# nabijecka.net
KiCad netlist of a schematic drawn in EAGLE
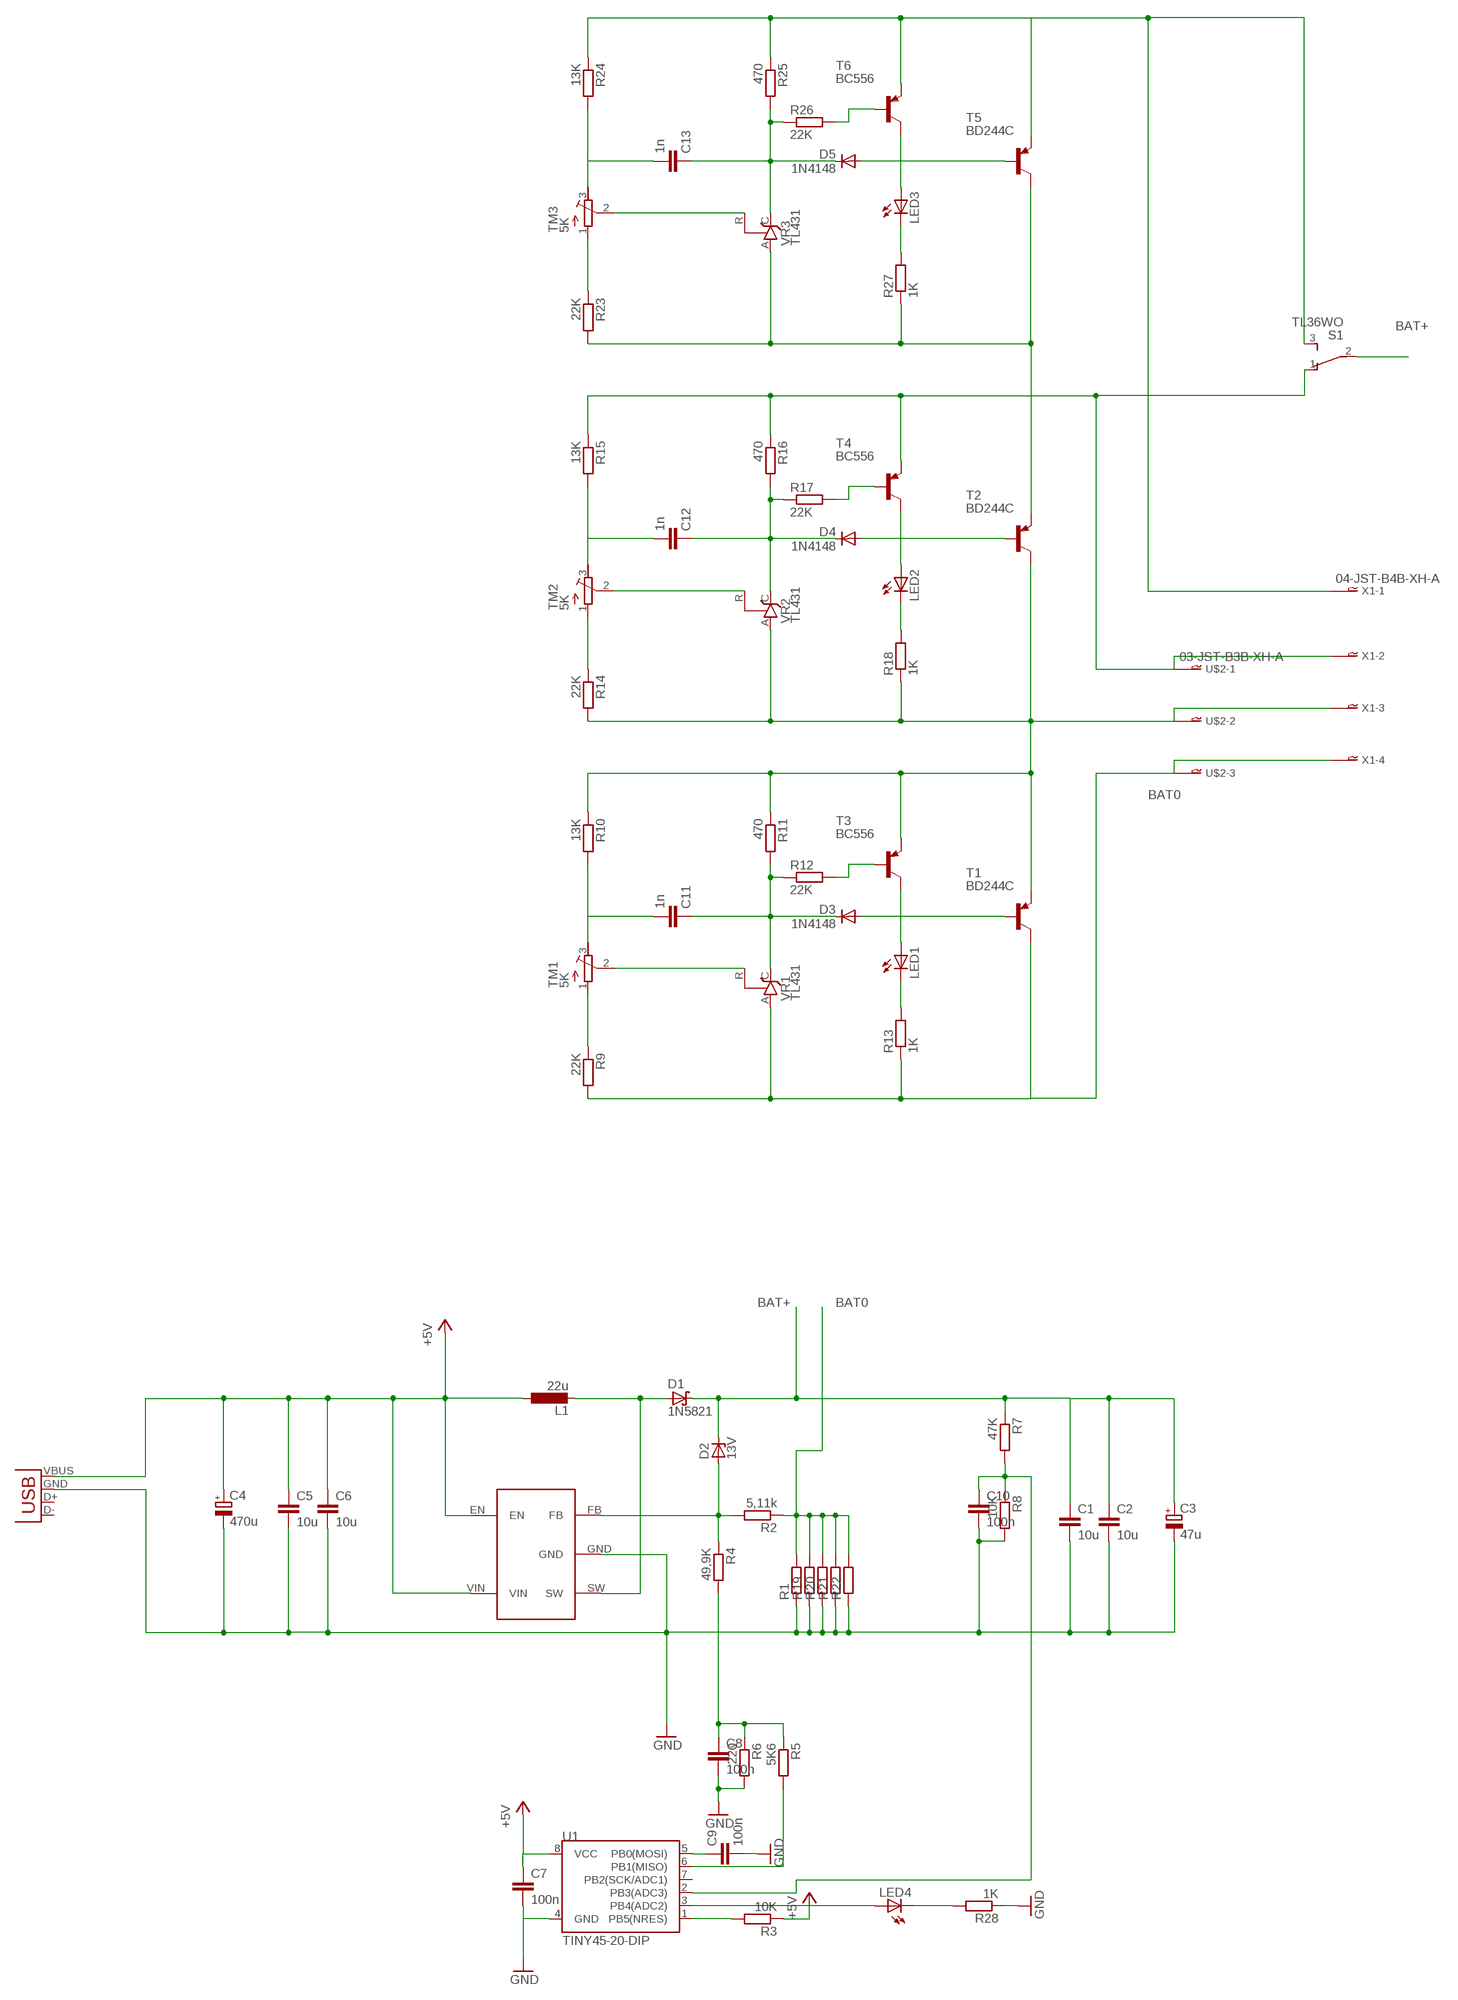
[diagram p0: schematic, sheet 1]

(export (version "E")
  (design (tool "Eeschema 10.0.6"))
  (components
    (comp (ref "C1")
      (value "10u")
      (footprint "eagle-import:C1206")
      (libsource (lib "eagle-import") (part "C-EUC1206"))
    )
    (comp (ref "C2")
      (value "10u")
      (footprint "eagle-import:C1206")
      (libsource (lib "eagle-import") (part "C-EUC1206"))
    )
    (comp (ref "C3")
      (value "47u")
      (footprint "eagle-import:E3,5-8")
      (libsource (lib "eagle-import") (part "CPOL-EUE3.5-8"))
    )
    (comp (ref "C4")
      (value "470u")
      (footprint "eagle-import:E3,5-8")
      (libsource (lib "eagle-import") (part "CPOL-EUE3.5-8"))
    )
    (comp (ref "C5")
      (value "10u")
      (footprint "eagle-import:C1206")
      (libsource (lib "eagle-import") (part "C-EUC1206"))
    )
    (comp (ref "C6")
      (value "10u")
      (footprint "eagle-import:C1206")
      (libsource (lib "eagle-import") (part "C-EUC1206"))
    )
    (comp (ref "C7")
      (value "100n")
      (footprint "eagle-import:C0805")
      (libsource (lib "eagle-import") (part "C-EUC0805"))
    )
    (comp (ref "C8")
      (value "100n")
      (footprint "eagle-import:C1206")
      (libsource (lib "eagle-import") (part "C-EUC1206"))
    )
    (comp (ref "C9")
      (value "100n")
      (footprint "eagle-import:C0805")
      (libsource (lib "eagle-import") (part "C-EUC0805"))
    )
    (comp (ref "C10")
      (value "100n")
      (footprint "eagle-import:C1206")
      (libsource (lib "eagle-import") (part "C-EUC1206"))
    )
    (comp (ref "C11")
      (value "1n")
      (footprint "eagle-import:C1206")
      (libsource (lib "eagle-import") (part "C-EUC1206"))
    )
    (comp (ref "C12")
      (value "1n")
      (footprint "eagle-import:C1206")
      (libsource (lib "eagle-import") (part "C-EUC1206"))
    )
    (comp (ref "C13")
      (value "1n")
      (footprint "eagle-import:C1206")
      (libsource (lib "eagle-import") (part "C-EUC1206"))
    )
    (comp (ref "D1")
      (value "1N5821")
      (footprint "eagle-import:DO35-7")
      (libsource (lib "eagle-import") (part "SCHOTTKY-DIODEDO35-7"))
    )
    (comp (ref "D2")
      (value "13V")
      (footprint "eagle-import:SOD80C")
      (libsource (lib "eagle-import") (part "ZENER-DIODESOD80C"))
    )
    (comp (ref "D3")
      (value "1N4148")
      (footprint "eagle-import:SOD80C")
      (libsource (lib "eagle-import") (part "DIODE-SOD80C"))
    )
    (comp (ref "D4")
      (value "1N4148")
      (footprint "eagle-import:SOD80C")
      (libsource (lib "eagle-import") (part "DIODE-SOD80C"))
    )
    (comp (ref "D5")
      (value "1N4148")
      (footprint "eagle-import:SOD80C")
      (libsource (lib "eagle-import") (part "DIODE-SOD80C"))
    )
    (comp (ref "JP2")
      (value "USB-A-H")
      (footprint "eagle-import:USB-A-H")
      (libsource (lib "eagle-import") (part "USB-A-H"))
    )
    (comp (ref "L1")
      (value "22u")
      (footprint "eagle-import:POWER-CHOKE_WE-TPC")
      (libsource (lib "eagle-import") (part "L-EUWE-TPC"))
    )
    (comp (ref "LED1")
      (value "LED3MM")
      (footprint "eagle-import:LED3MM")
      (libsource (lib "eagle-import") (part "LED3MM"))
    )
    (comp (ref "LED2")
      (value "LED3MM")
      (footprint "eagle-import:LED3MM")
      (libsource (lib "eagle-import") (part "LED3MM"))
    )
    (comp (ref "LED3")
      (value "LED3MM")
      (footprint "eagle-import:LED3MM")
      (libsource (lib "eagle-import") (part "LED3MM"))
    )
    (comp (ref "LED4")
      (value "LED3MM")
      (footprint "eagle-import:LED3MM")
      (libsource (lib "eagle-import") (part "LED3MM"))
    )
    (comp (ref "R1")
      (value "R-EU_0204/7")
      (footprint "eagle-import:0204_7")
      (libsource (lib "eagle-import") (part "R-EU_0204/7"))
    )
    (comp (ref "R2")
      (value "5,11k")
      (footprint "eagle-import:0204_5")
      (libsource (lib "eagle-import") (part "R-EU_0204/5"))
    )
    (comp (ref "R3")
      (value "10K")
      (footprint "eagle-import:R0805")
      (libsource (lib "eagle-import") (part "R-EU_R0805"))
    )
    (comp (ref "R4")
      (value "49,9K")
      (footprint "eagle-import:0204_5")
      (libsource (lib "eagle-import") (part "R-EU_0204/5"))
    )
    (comp (ref "R5")
      (value "5K6")
      (footprint "eagle-import:R1206")
      (libsource (lib "eagle-import") (part "R-EU_R1206"))
    )
    (comp (ref "R6")
      (value "220")
      (footprint "eagle-import:R1206")
      (libsource (lib "eagle-import") (part "R-EU_R1206"))
    )
    (comp (ref "R7")
      (value "47K")
      (footprint "eagle-import:R1206")
      (libsource (lib "eagle-import") (part "R-EU_R1206"))
    )
    (comp (ref "R8")
      (value "10K")
      (footprint "eagle-import:R1206")
      (libsource (lib "eagle-import") (part "R-EU_R1206"))
    )
    (comp (ref "R9")
      (value "22K")
      (footprint "eagle-import:R1206")
      (libsource (lib "eagle-import") (part "R-EU_R1206"))
    )
    (comp (ref "R10")
      (value "13K")
      (footprint "eagle-import:R1206")
      (libsource (lib "eagle-import") (part "R-EU_R1206"))
    )
    (comp (ref "R11")
      (value "470")
      (footprint "eagle-import:R1206")
      (libsource (lib "eagle-import") (part "R-EU_R1206"))
    )
    (comp (ref "R12")
      (value "22K")
      (footprint "eagle-import:R0805")
      (libsource (lib "eagle-import") (part "R-EU_R0805"))
    )
    (comp (ref "R13")
      (value "1K")
      (footprint "eagle-import:R1206")
      (libsource (lib "eagle-import") (part "R-EU_R1206"))
    )
    (comp (ref "R14")
      (value "22K")
      (footprint "eagle-import:R1206")
      (libsource (lib "eagle-import") (part "R-EU_R1206"))
    )
    (comp (ref "R15")
      (value "13K")
      (footprint "eagle-import:R1206")
      (libsource (lib "eagle-import") (part "R-EU_R1206"))
    )
    (comp (ref "R16")
      (value "470")
      (footprint "eagle-import:R1206")
      (libsource (lib "eagle-import") (part "R-EU_R1206"))
    )
    (comp (ref "R17")
      (value "22K")
      (footprint "eagle-import:R0805")
      (libsource (lib "eagle-import") (part "R-EU_R0805"))
    )
    (comp (ref "R18")
      (value "1K")
      (footprint "eagle-import:R1206")
      (libsource (lib "eagle-import") (part "R-EU_R1206"))
    )
    (comp (ref "R19")
      (value "R-EU_0204/7")
      (footprint "eagle-import:0204_7")
      (libsource (lib "eagle-import") (part "R-EU_0204/7"))
    )
    (comp (ref "R20")
      (value "R-EU_0204/7")
      (footprint "eagle-import:0204_7")
      (libsource (lib "eagle-import") (part "R-EU_0204/7"))
    )
    (comp (ref "R21")
      (value "R-EU_0204/7")
      (footprint "eagle-import:0204_7")
      (libsource (lib "eagle-import") (part "R-EU_0204/7"))
    )
    (comp (ref "R22")
      (value "R-EU_0204/7")
      (footprint "eagle-import:0204_7")
      (libsource (lib "eagle-import") (part "R-EU_0204/7"))
    )
    (comp (ref "R23")
      (value "22K")
      (footprint "eagle-import:R1206")
      (libsource (lib "eagle-import") (part "R-EU_R1206"))
    )
    (comp (ref "R24")
      (value "13K")
      (footprint "eagle-import:R1206")
      (libsource (lib "eagle-import") (part "R-EU_R1206"))
    )
    (comp (ref "R25")
      (value "470")
      (footprint "eagle-import:R1206")
      (libsource (lib "eagle-import") (part "R-EU_R1206"))
    )
    (comp (ref "R26")
      (value "22K")
      (footprint "eagle-import:R0805")
      (libsource (lib "eagle-import") (part "R-EU_R0805"))
    )
    (comp (ref "R27")
      (value "1K")
      (footprint "eagle-import:R1206")
      (libsource (lib "eagle-import") (part "R-EU_R1206"))
    )
    (comp (ref "R28")
      (value "1K")
      (footprint "eagle-import:R1206")
      (libsource (lib "eagle-import") (part "R-EU_R1206"))
    )
    (comp (ref "S1")
      (value "TL36WO")
      (footprint "eagle-import:TL3XWO")
      (libsource (lib "eagle-import") (part "TL36WO"))
    )
    (comp (ref "T1")
      (value "BD244C")
      (footprint "eagle-import:TO220")
      (libsource (lib "eagle-import") (part "-PNP-TO220"))
    )
    (comp (ref "T2")
      (value "BD244C")
      (footprint "eagle-import:TO220")
      (libsource (lib "eagle-import") (part "-PNP-TO220"))
    )
    (comp (ref "T3")
      (value "BC556")
      (footprint "eagle-import:TO92-EBC")
      (libsource (lib "eagle-import") (part "-PNP-TO92-EBCBC556B"))
    )
    (comp (ref "T4")
      (value "BC556")
      (footprint "eagle-import:TO92-EBC")
      (libsource (lib "eagle-import") (part "-PNP-TO92-EBCBC556B"))
    )
    (comp (ref "T5")
      (value "BD244C")
      (footprint "eagle-import:TO220")
      (libsource (lib "eagle-import") (part "-PNP-TO220"))
    )
    (comp (ref "T6")
      (value "BC556")
      (footprint "eagle-import:TO92-EBC")
      (libsource (lib "eagle-import") (part "-PNP-TO92-EBCBC556B"))
    )
    (comp (ref "TM1")
      (value "5K")
      (footprint "eagle-import:RTRIM64P")
      (libsource (lib "eagle-import") (part "R-TRIMM64P"))
    )
    (comp (ref "TM2")
      (value "5K")
      (footprint "eagle-import:RTRIM64P")
      (libsource (lib "eagle-import") (part "R-TRIMM64P"))
    )
    (comp (ref "TM3")
      (value "5K")
      (footprint "eagle-import:RTRIM64P")
      (libsource (lib "eagle-import") (part "R-TRIMM64P"))
    )
    (comp (ref "U$1")
      (value "MIC2287")
      (footprint "eagle-import:MIC2287")
      (libsource (lib "eagle-import") (part "MIC2287"))
    )
    (comp (ref "U$2")
      (value "03-JST-B3B-XH-A")
      (footprint "eagle-import:B3B-XH")
      (libsource (lib "eagle-import") (part "03-JST-B3B-XH-A"))
    )
    (comp (ref "U1")
      (value "TINY45-20-DIP")
      (footprint "eagle-import:DIP08")
      (libsource (lib "eagle-import") (part "ATTINY45TINY45-20-DIP"))
    )
    (comp (ref "VR1")
      (value "TL431")
      (footprint "eagle-import:TO92-CLP")
      (libsource (lib "eagle-import") (part "TL431CLP"))
    )
    (comp (ref "VR2")
      (value "TL431")
      (footprint "eagle-import:TO92-CLP")
      (libsource (lib "eagle-import") (part "TL431CLP"))
    )
    (comp (ref "VR3")
      (value "TL431")
      (footprint "eagle-import:TO92-CLP")
      (libsource (lib "eagle-import") (part "TL431CLP"))
    )
    (comp (ref "X1")
      (value "04-JST-B4B-XH-A")
      (footprint "eagle-import:B4B-XH")
      (libsource (lib "eagle-import") (part "04-JST-B4B-XH-A"))
    )
  )
  (nets
    (net (code "1") (name "+5V") (class "Default")
      (node (ref "C4") (pin "+") (pinfunction "+_+") (pintype "passive"))
      (node (ref "C5") (pin "1") (pinfunction "1_1") (pintype "passive"))
      (node (ref "C6") (pin "1") (pinfunction "1_1") (pintype "passive"))
      (node (ref "C7") (pin "1") (pinfunction "1_1") (pintype "passive"))
      (node (ref "JP2") (pin "VBUS") (pinfunction "GND_VBUS") (pintype "bidirectional"))
      (node (ref "L1") (pin "1") (pinfunction "1_1") (pintype "passive"))
      (node (ref "R3") (pin "1") (pinfunction "1_1") (pintype "passive"))
      (node (ref "U$1") (pin "EN") (pinfunction "EN_EN") (pintype "bidirectional"))
      (node (ref "U$1") (pin "VIN") (pinfunction "VIN_VIN") (pintype "bidirectional"))
      (node (ref "U1") (pin "8") (pinfunction "VCC_8") (pintype "bidirectional"))
    )
    (net (code "2") (name "/BAT+") (class "Default")
      (node (ref "C1") (pin "1") (pinfunction "1_1") (pintype "passive"))
      (node (ref "C2") (pin "1") (pinfunction "1_1") (pintype "passive"))
      (node (ref "C3") (pin "+") (pinfunction "+_+") (pintype "passive"))
      (node (ref "D1") (pin "C") (pinfunction "C_C") (pintype "passive"))
      (node (ref "D2") (pin "C") (pinfunction "C_C") (pintype "passive"))
      (node (ref "R7") (pin "1") (pinfunction "1_1") (pintype "passive"))
      (node (ref "S1") (pin "2") (pinfunction "P_2") (pintype "passive"))
    )
    (net (code "3") (name "/BAT0") (class "Default")
      (node (ref "R1") (pin "2") (pinfunction "2_2") (pintype "passive"))
      (node (ref "R13") (pin "1") (pinfunction "1_1") (pintype "passive"))
      (node (ref "R19") (pin "2") (pinfunction "2_2") (pintype "passive"))
      (node (ref "R2") (pin "1") (pinfunction "1_1") (pintype "passive"))
      (node (ref "R20") (pin "2") (pinfunction "2_2") (pintype "passive"))
      (node (ref "R21") (pin "2") (pinfunction "2_2") (pintype "passive"))
      (node (ref "R22") (pin "2") (pinfunction "2_2") (pintype "passive"))
      (node (ref "R9") (pin "2") (pinfunction "2_2") (pintype "passive"))
      (node (ref "T1") (pin "2") (pinfunction "C_2") (pintype "passive"))
      (node (ref "U$2") (pin "P$3") (pinfunction "1_P$3") (pintype "passive"))
      (node (ref "VR1") (pin "A") (pinfunction "A_A") (pintype "passive"))
      (node (ref "X1") (pin "P$4") (pinfunction "1_P$4") (pintype "passive"))
    )
    (net (code "4") (name "GND") (class "Default")
      (node (ref "C1") (pin "2") (pinfunction "2_2") (pintype "passive"))
      (node (ref "C10") (pin "2") (pinfunction "2_2") (pintype "passive"))
      (node (ref "C2") (pin "2") (pinfunction "2_2") (pintype "passive"))
      (node (ref "C3") (pin "-") (pinfunction "-_-") (pintype "passive"))
      (node (ref "C4") (pin "-") (pinfunction "-_-") (pintype "passive"))
      (node (ref "C5") (pin "2") (pinfunction "2_2") (pintype "passive"))
      (node (ref "C6") (pin "2") (pinfunction "2_2") (pintype "passive"))
      (node (ref "C7") (pin "2") (pinfunction "2_2") (pintype "passive"))
      (node (ref "C8") (pin "2") (pinfunction "2_2") (pintype "passive"))
      (node (ref "C9") (pin "2") (pinfunction "2_2") (pintype "passive"))
      (node (ref "JP2") (pin "GND") (pinfunction "VBUS_GND") (pintype "bidirectional"))
      (node (ref "R1") (pin "1") (pinfunction "1_1") (pintype "passive"))
      (node (ref "R19") (pin "1") (pinfunction "1_1") (pintype "passive"))
      (node (ref "R20") (pin "1") (pinfunction "1_1") (pintype "passive"))
      (node (ref "R21") (pin "1") (pinfunction "1_1") (pintype "passive"))
      (node (ref "R22") (pin "1") (pinfunction "1_1") (pintype "passive"))
      (node (ref "R28") (pin "1") (pinfunction "1_1") (pintype "passive"))
      (node (ref "R6") (pin "2") (pinfunction "2_2") (pintype "passive"))
      (node (ref "R8") (pin "2") (pinfunction "2_2") (pintype "passive"))
      (node (ref "U$1") (pin "GND") (pinfunction "GND_GND") (pintype "bidirectional"))
      (node (ref "U1") (pin "4") (pinfunction "GND_4") (pintype "bidirectional"))
    )
    (net (code "5") (name "Net-(C8-Pad1)") (class "Default")
      (node (ref "C8") (pin "1") (pinfunction "1_1") (pintype "passive"))
      (node (ref "R4") (pin "2") (pinfunction "2_2") (pintype "passive"))
      (node (ref "R5") (pin "1") (pinfunction "1_1") (pintype "passive"))
      (node (ref "R6") (pin "1") (pinfunction "1_1") (pintype "passive"))
    )
    (net (code "6") (name "Net-(C11-Pad1)") (class "Default")
      (node (ref "C11") (pin "1") (pinfunction "1_1") (pintype "passive"))
      (node (ref "D3") (pin "C") (pinfunction "C_C") (pintype "passive"))
      (node (ref "R11") (pin "2") (pinfunction "2_2") (pintype "passive"))
      (node (ref "R12") (pin "1") (pinfunction "1_1") (pintype "passive"))
      (node (ref "VR1") (pin "C") (pinfunction "C_C") (pintype "passive"))
    )
    (net (code "7") (name "Net-(C12-Pad1)") (class "Default")
      (node (ref "C12") (pin "1") (pinfunction "1_1") (pintype "passive"))
      (node (ref "D4") (pin "C") (pinfunction "C_C") (pintype "passive"))
      (node (ref "R16") (pin "2") (pinfunction "2_2") (pintype "passive"))
      (node (ref "R17") (pin "1") (pinfunction "1_1") (pintype "passive"))
      (node (ref "VR2") (pin "C") (pinfunction "C_C") (pintype "passive"))
    )
    (net (code "8") (name "Net-(C13-Pad1)") (class "Default")
      (node (ref "C13") (pin "1") (pinfunction "1_1") (pintype "passive"))
      (node (ref "D5") (pin "C") (pinfunction "C_C") (pintype "passive"))
      (node (ref "R25") (pin "2") (pinfunction "2_2") (pintype "passive"))
      (node (ref "R26") (pin "1") (pinfunction "1_1") (pintype "passive"))
      (node (ref "VR3") (pin "C") (pinfunction "C_C") (pintype "passive"))
    )
    (net (code "9") (name "Net-(D1-PadA)") (class "Default")
      (node (ref "D1") (pin "A") (pinfunction "A_A") (pintype "passive"))
      (node (ref "L1") (pin "2") (pinfunction "2_2") (pintype "passive"))
      (node (ref "U$1") (pin "SW") (pinfunction "SW_SW") (pintype "bidirectional"))
    )
    (net (code "10") (name "Net-(D2-PadA)") (class "Default")
      (node (ref "D2") (pin "A") (pinfunction "A_A") (pintype "passive"))
      (node (ref "R2") (pin "2") (pinfunction "2_2") (pintype "passive"))
      (node (ref "R4") (pin "1") (pinfunction "1_1") (pintype "passive"))
      (node (ref "U$1") (pin "FB") (pinfunction "FB_FB") (pintype "bidirectional"))
    )
    (net (code "11") (name "Net-(LED1-C)") (class "Default")
      (node (ref "LED1") (pin "K") (pinfunction "C_K") (pintype "passive"))
      (node (ref "R13") (pin "2") (pinfunction "2_2") (pintype "passive"))
    )
    (net (code "12") (name "Net-(LED1-PadA)") (class "Default")
      (node (ref "LED1") (pin "A") (pinfunction "A_A") (pintype "passive"))
      (node (ref "T3") (pin "C") (pinfunction "C_C") (pintype "passive"))
    )
    (net (code "13") (name "Net-(LED2-C)") (class "Default")
      (node (ref "LED2") (pin "K") (pinfunction "C_K") (pintype "passive"))
      (node (ref "R18") (pin "2") (pinfunction "2_2") (pintype "passive"))
    )
    (net (code "14") (name "Net-(LED2-PadA)") (class "Default")
      (node (ref "LED2") (pin "A") (pinfunction "A_A") (pintype "passive"))
      (node (ref "T4") (pin "C") (pinfunction "C_C") (pintype "passive"))
    )
    (net (code "15") (name "Net-(LED3-C)") (class "Default")
      (node (ref "LED3") (pin "K") (pinfunction "C_K") (pintype "passive"))
      (node (ref "R27") (pin "2") (pinfunction "2_2") (pintype "passive"))
    )
    (net (code "16") (name "Net-(LED3-PadA)") (class "Default")
      (node (ref "LED3") (pin "A") (pinfunction "A_A") (pintype "passive"))
      (node (ref "T6") (pin "C") (pinfunction "C_C") (pintype "passive"))
    )
    (net (code "17") (name "Net-(LED4-C)") (class "Default")
      (node (ref "LED4") (pin "K") (pinfunction "C_K") (pintype "passive"))
      (node (ref "R28") (pin "2") (pinfunction "2_2") (pintype "passive"))
    )
    (net (code "18") (name "Net-(R12-Pad2)") (class "Default")
      (node (ref "R12") (pin "2") (pinfunction "2_2") (pintype "passive"))
      (node (ref "T3") (pin "B") (pinfunction "B_B") (pintype "passive"))
    )
    (net (code "19") (name "Net-(R17-Pad2)") (class "Default")
      (node (ref "R17") (pin "2") (pinfunction "2_2") (pintype "passive"))
      (node (ref "T4") (pin "B") (pinfunction "B_B") (pintype "passive"))
    )
    (net (code "20") (name "Net-(R26-Pad2)") (class "Default")
      (node (ref "R26") (pin "2") (pinfunction "2_2") (pintype "passive"))
      (node (ref "T6") (pin "B") (pinfunction "B_B") (pintype "passive"))
    )
    (net (code "21") (name "Net-(S1-O)") (class "Default")
      (node (ref "R15") (pin "1") (pinfunction "1_1") (pintype "passive"))
      (node (ref "R16") (pin "1") (pinfunction "1_1") (pintype "passive"))
      (node (ref "R23") (pin "2") (pinfunction "2_2") (pintype "passive"))
      (node (ref "R27") (pin "1") (pinfunction "1_1") (pintype "passive"))
      (node (ref "S1") (pin "1") (pinfunction "O_1") (pintype "passive"))
      (node (ref "T2") (pin "3") (pinfunction "E_3") (pintype "passive"))
      (node (ref "T4") (pin "E") (pinfunction "E_E") (pintype "passive"))
      (node (ref "T5") (pin "2") (pinfunction "C_2") (pintype "passive"))
      (node (ref "U$2") (pin "P$1") (pinfunction "1_P$1") (pintype "passive"))
      (node (ref "VR3") (pin "A") (pinfunction "A_A") (pintype "passive"))
      (node (ref "X1") (pin "P$2") (pinfunction "1_P$2") (pintype "passive"))
    )
    (net (code "22") (name "Net-(S1-S)") (class "Default")
      (node (ref "R24") (pin "1") (pinfunction "1_1") (pintype "passive"))
      (node (ref "R25") (pin "1") (pinfunction "1_1") (pintype "passive"))
      (node (ref "S1") (pin "3") (pinfunction "S_3") (pintype "passive"))
      (node (ref "T5") (pin "3") (pinfunction "E_3") (pintype "passive"))
      (node (ref "T6") (pin "E") (pinfunction "E_E") (pintype "passive"))
      (node (ref "X1") (pin "P$1") (pinfunction "1_P$1") (pintype "passive"))
    )
    (net (code "23") (name "Net-(T1-B)") (class "Default")
      (node (ref "D3") (pin "A") (pinfunction "A_A") (pintype "passive"))
      (node (ref "T1") (pin "1") (pinfunction "B_1") (pintype "passive"))
    )
    (net (code "24") (name "Net-(T1-E)") (class "Default")
      (node (ref "R10") (pin "1") (pinfunction "1_1") (pintype "passive"))
      (node (ref "R11") (pin "1") (pinfunction "1_1") (pintype "passive"))
      (node (ref "R14") (pin "2") (pinfunction "2_2") (pintype "passive"))
      (node (ref "R18") (pin "1") (pinfunction "1_1") (pintype "passive"))
      (node (ref "T1") (pin "3") (pinfunction "E_3") (pintype "passive"))
      (node (ref "T2") (pin "2") (pinfunction "C_2") (pintype "passive"))
      (node (ref "T3") (pin "E") (pinfunction "E_E") (pintype "passive"))
      (node (ref "U$2") (pin "P$2") (pinfunction "1_P$2") (pintype "passive"))
      (node (ref "VR2") (pin "A") (pinfunction "A_A") (pintype "passive"))
      (node (ref "X1") (pin "P$3") (pinfunction "1_P$3") (pintype "passive"))
    )
    (net (code "25") (name "Net-(T2-B)") (class "Default")
      (node (ref "D4") (pin "A") (pinfunction "A_A") (pintype "passive"))
      (node (ref "T2") (pin "1") (pinfunction "B_1") (pintype "passive"))
    )
    (net (code "26") (name "Net-(T5-B)") (class "Default")
      (node (ref "D5") (pin "A") (pinfunction "A_A") (pintype "passive"))
      (node (ref "T5") (pin "1") (pinfunction "B_1") (pintype "passive"))
    )
    (net (code "27") (name "Net-(TM1-A)") (class "Default")
      (node (ref "C11") (pin "2") (pinfunction "2_2") (pintype "passive"))
      (node (ref "R10") (pin "2") (pinfunction "2_2") (pintype "passive"))
      (node (ref "TM1") (pin "3") (pinfunction "A_3") (pintype "passive"))
    )
    (net (code "28") (name "Net-(TM1-E)") (class "Default")
      (node (ref "R9") (pin "1") (pinfunction "1_1") (pintype "passive"))
      (node (ref "TM1") (pin "1") (pinfunction "E_1") (pintype "passive"))
    )
    (net (code "29") (name "Net-(TM1-S)") (class "Default")
      (node (ref "TM1") (pin "2") (pinfunction "S_2") (pintype "passive"))
      (node (ref "VR1") (pin "R") (pinfunction "R_R") (pintype "passive"))
    )
    (net (code "30") (name "Net-(TM2-A)") (class "Default")
      (node (ref "C12") (pin "2") (pinfunction "2_2") (pintype "passive"))
      (node (ref "R15") (pin "2") (pinfunction "2_2") (pintype "passive"))
      (node (ref "TM2") (pin "3") (pinfunction "A_3") (pintype "passive"))
    )
    (net (code "31") (name "Net-(TM2-E)") (class "Default")
      (node (ref "R14") (pin "1") (pinfunction "1_1") (pintype "passive"))
      (node (ref "TM2") (pin "1") (pinfunction "E_1") (pintype "passive"))
    )
    (net (code "32") (name "Net-(TM2-S)") (class "Default")
      (node (ref "TM2") (pin "2") (pinfunction "S_2") (pintype "passive"))
      (node (ref "VR2") (pin "R") (pinfunction "R_R") (pintype "passive"))
    )
    (net (code "33") (name "Net-(TM3-A)") (class "Default")
      (node (ref "C13") (pin "2") (pinfunction "2_2") (pintype "passive"))
      (node (ref "R24") (pin "2") (pinfunction "2_2") (pintype "passive"))
      (node (ref "TM3") (pin "3") (pinfunction "A_3") (pintype "passive"))
    )
    (net (code "34") (name "Net-(TM3-E)") (class "Default")
      (node (ref "R23") (pin "1") (pinfunction "1_1") (pintype "passive"))
      (node (ref "TM3") (pin "1") (pinfunction "E_1") (pintype "passive"))
    )
    (net (code "35") (name "Net-(TM3-S)") (class "Default")
      (node (ref "TM3") (pin "2") (pinfunction "S_2") (pintype "passive"))
      (node (ref "VR3") (pin "R") (pinfunction "R_R") (pintype "passive"))
    )
    (net (code "36") (name "Net-(U1-PB0(MOSI))") (class "Default")
      (node (ref "C9") (pin "1") (pinfunction "1_1") (pintype "passive"))
      (node (ref "U1") (pin "5") (pinfunction "PB0(MOSI)_5") (pintype "bidirectional"))
    )
    (net (code "37") (name "Net-(U1-PB1(MISO))") (class "Default")
      (node (ref "R5") (pin "2") (pinfunction "2_2") (pintype "passive"))
      (node (ref "U1") (pin "6") (pinfunction "PB1(MISO)_6") (pintype "bidirectional"))
    )
    (net (code "38") (name "Net-(U1-PB3(ADC3))") (class "Default")
      (node (ref "C10") (pin "1") (pinfunction "1_1") (pintype "passive"))
      (node (ref "R7") (pin "2") (pinfunction "2_2") (pintype "passive"))
      (node (ref "R8") (pin "1") (pinfunction "1_1") (pintype "passive"))
      (node (ref "U1") (pin "2") (pinfunction "PB3(ADC3)_2") (pintype "bidirectional"))
    )
    (net (code "39") (name "Net-(U1-PB4(ADC2))") (class "Default")
      (node (ref "LED4") (pin "A") (pinfunction "A_A") (pintype "passive"))
      (node (ref "U1") (pin "3") (pinfunction "PB4(ADC2)_3") (pintype "bidirectional"))
    )
    (net (code "40") (name "Net-(U1-PB5(NRES))") (class "Default")
      (node (ref "R3") (pin "2") (pinfunction "2_2") (pintype "passive"))
      (node (ref "U1") (pin "1") (pinfunction "PB5(NRES)_1") (pintype "bidirectional"))
    )
    (net (code "41") (name "unconnected-(JP2-D+-PadD-)") (class "Default")
      (node (ref "JP2") (pin "D-") (pinfunction "D+_D-") (pintype "bidirectional"))
    )
    (net (code "42") (name "unconnected-(JP2-D--PadD+)") (class "Default")
      (node (ref "JP2") (pin "D+") (pinfunction "D-_D+") (pintype "bidirectional"))
    )
    (net (code "43") (name "unconnected-(U1-PB2(SCK{slash}ADC1)-Pad7)") (class "Default")
      (node (ref "U1") (pin "7") (pinfunction "PB2(SCK/ADC1)_7") (pintype "bidirectional"))
    )
  )
)
